# 1-Schematic_ESP32_expandable_Power.net
KiCad netlist of a schematic drawn in EasyEDA
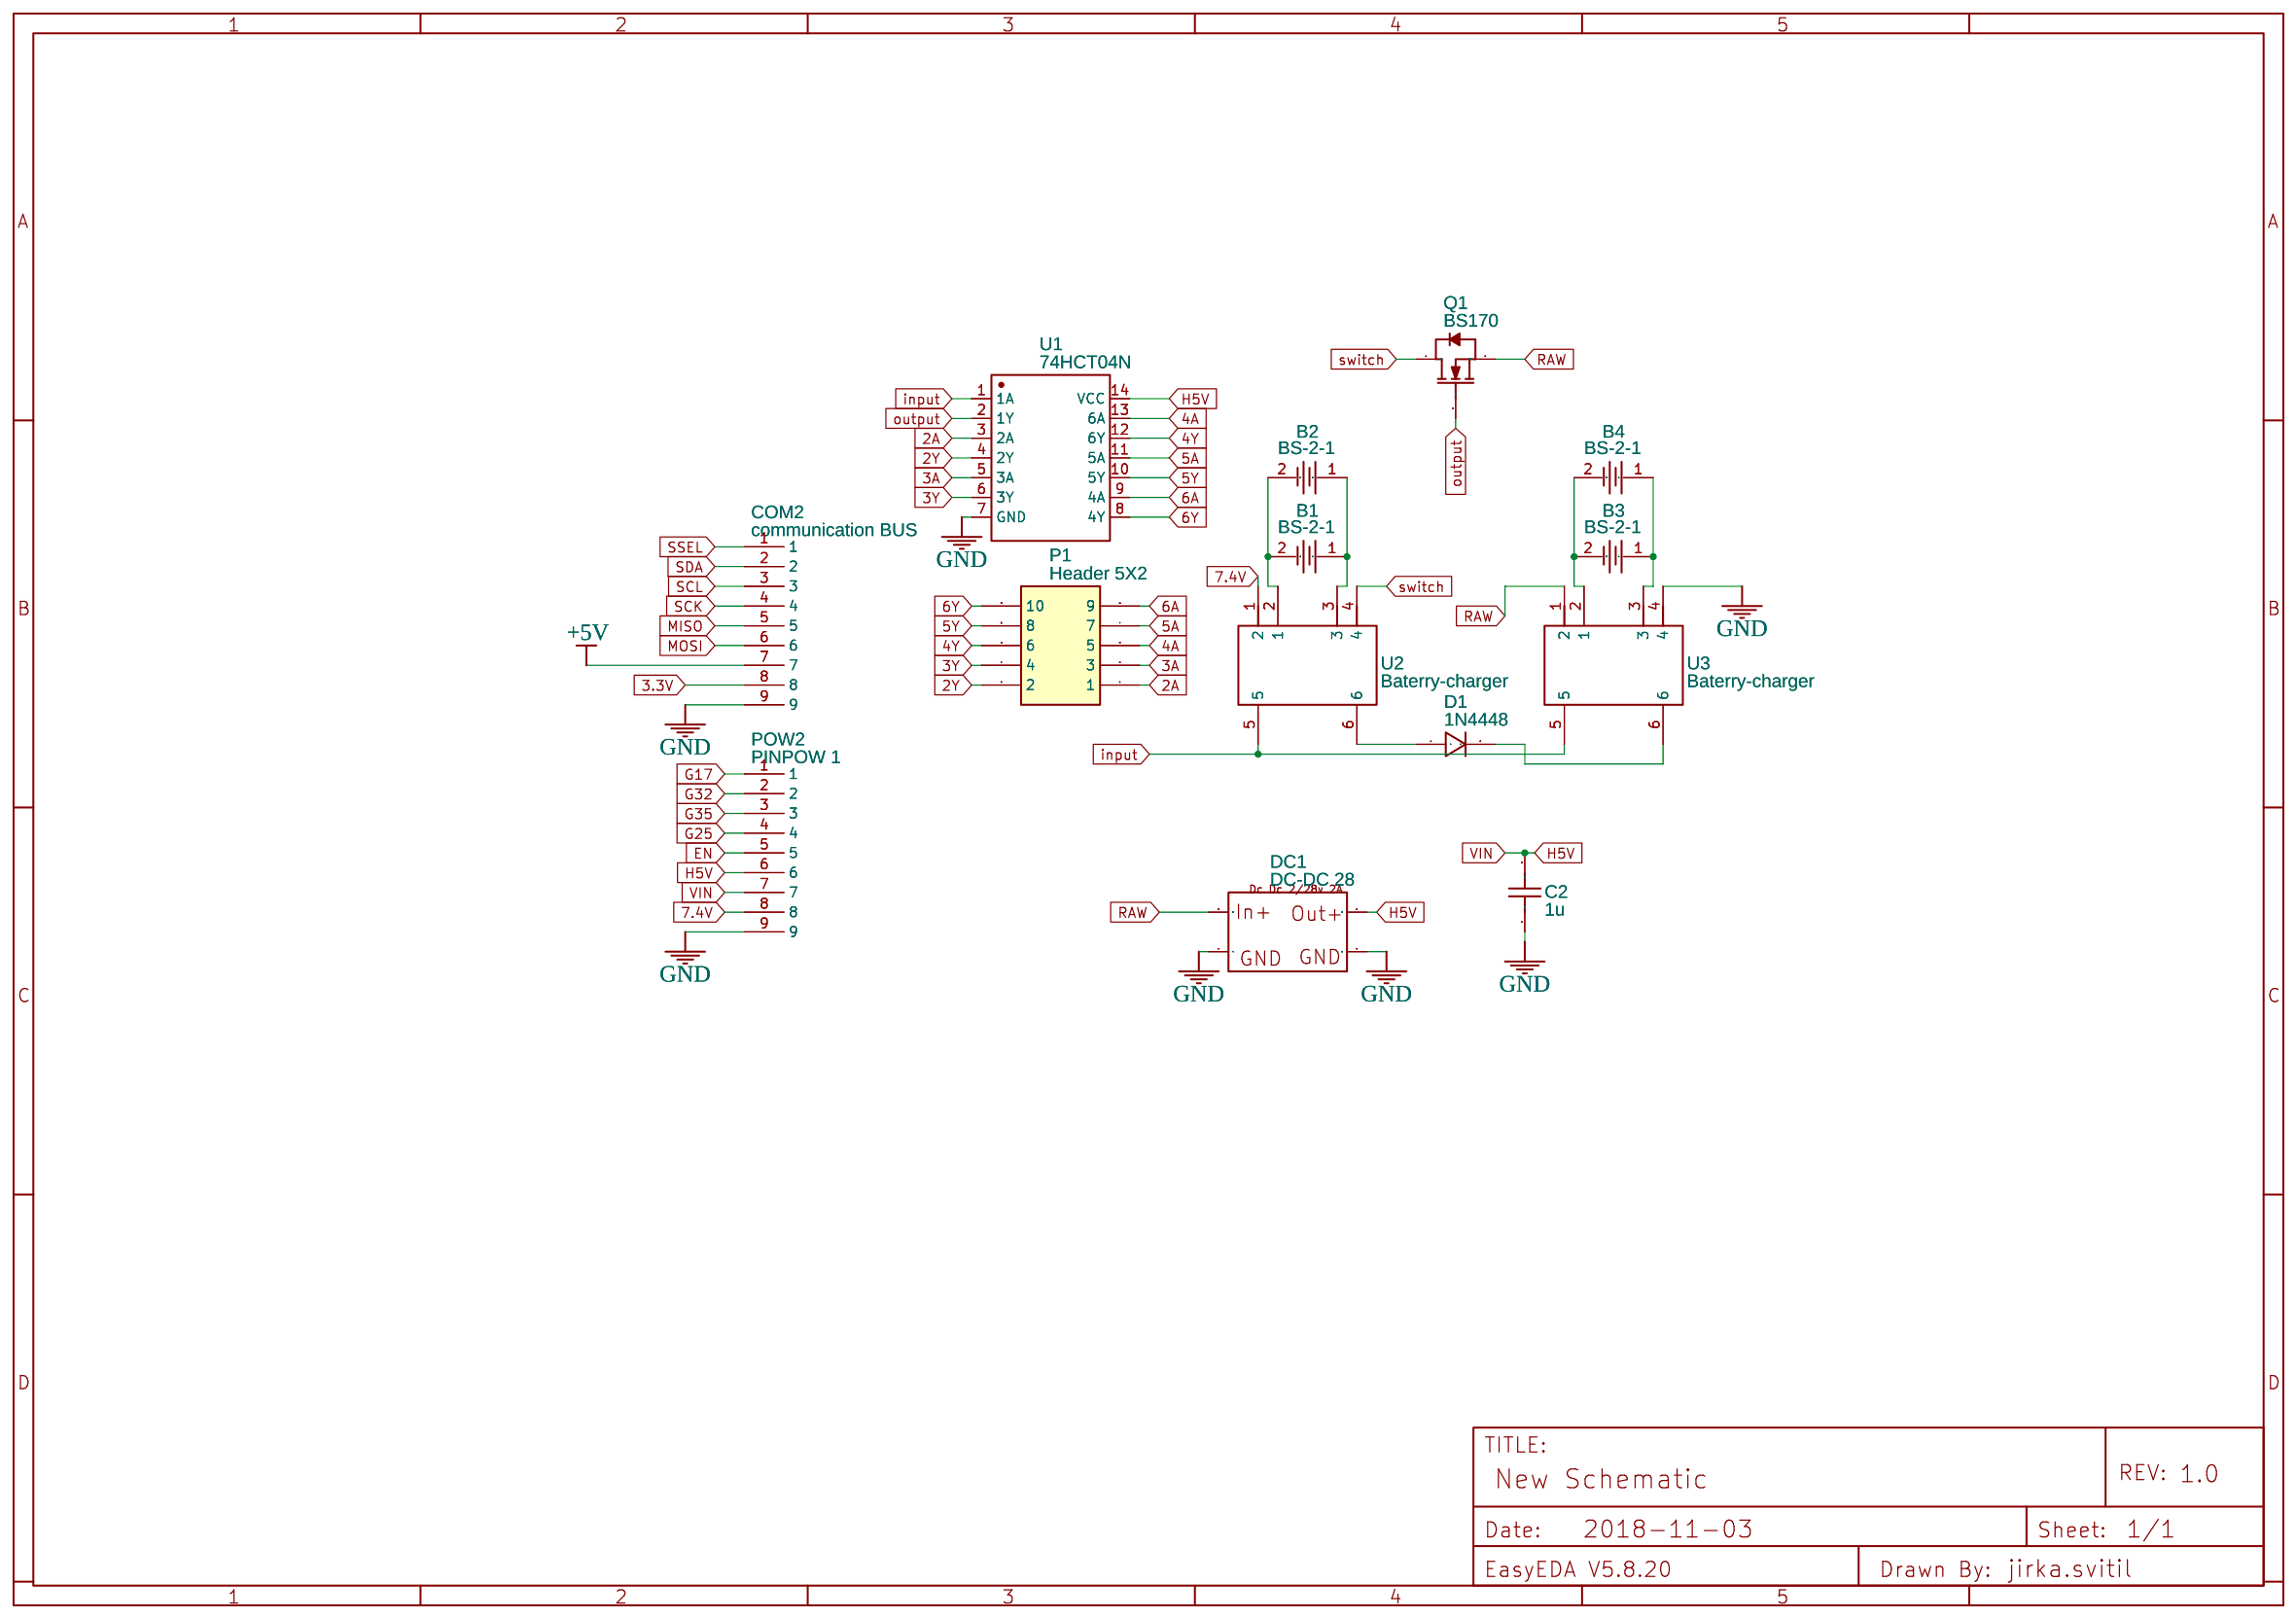
[diagram p0: schematic sheet]

(export (version "E")
  (design (tool "Eeschema 10.0.6"))
  (components
    (comp (ref "B1")
      (value "BS-2-1")
      (fields (field (name "BOM_Supplier Part") "C70376"))
      (libsource (lib "") (part "Unknown_655_275"))
    )
    (comp (ref "B2")
      (value "BS-2-1")
      (fields (field (name "BOM_Supplier Part") "C70376"))
      (libsource (lib "") (part "Unknown_655_235"))
    )
    (comp (ref "B3")
      (value "BS-2-1")
      (fields (field (name "BOM_Supplier Part") "C70376"))
      (libsource (lib "") (part "Unknown_810_275"))
    )
    (comp (ref "B4")
      (value "BS-2-1")
      (fields (field (name "BOM_Supplier Part") "C70376"))
      (libsource (lib "") (part "Unknown_810_235"))
    )
    (comp (ref "C2")
      (value "1u")
      (fields (field (name "BOM_Manufacturer Part") "?"))
      (libsource (lib "") (part "Cap_RAD-0.1_US"))
    )
    (comp (ref "COM2")
      (value "communication BUS")
      (fields (field (name "BOM_Manufacturer Part") "?"))
      (libsource (lib "") (part "Unknown_400_260"))
    )
    (comp (ref "D1")
      (value "1N4448")
      (fields (field (name "BOM_Supplier Part") "C54037"))
      (libsource (lib "") (part "Unknown_730_370"))
    )
    (comp (ref "DC1")
      (value "DC-DC 28")
      (fields (field (name "BOM_Manufacturer Part") "?"))
      (libsource (lib "") (part "DC-DC 28"))
    )
    (comp (ref "P1")
      (value "Header 5X2")
      (fields (field (name "BOM_Manufacturer Part") "?"))
      (libsource (lib "") (part "Unknown_530_320"))
    )
    (comp (ref "POW2")
      (value "PINPOW 1")
      (fields (field (name "BOM_Manufacturer Part") "?"))
      (libsource (lib "") (part "Unknown_400_375"))
    )
    (comp (ref "Q1")
      (value "BS170")
      (fields (field (name "BOM_Supplier Part") "C111691"))
      (libsource (lib "") (part "Unknown_730_175"))
    )
    (comp (ref "U1")
      (value "74HCT04N")
      (fields (field (name "BOM_Manufacturer Part") "?"))
      (libsource (lib "") (part "Unknown_525_185"))
    )
    (comp (ref "U2")
      (value "Baterry-charger")
      (fields (field (name "BOM_Manufacturer Part") "New SchematicLib"))
      (libsource (lib "") (part "Unknown_650_330"))
    )
    (comp (ref "U3")
      (value "Baterry-charger")
      (fields (field (name "BOM_Manufacturer Part") "New SchematicLib"))
      (libsource (lib "") (part "Unknown_805_330"))
    )
  )
  (nets
    (net (code "1") (name "+5V") (class "Default")
      (node (ref "COM2") (pin "7") (pinfunction "7_7") (pintype "unspecified"))
    )
    (net (code "2") (name "2A") (class "Default")
      (node (ref "P1") (pin "1") (pinfunction "1_1") (pintype "unspecified"))
      (node (ref "U1") (pin "3") (pinfunction "2A_3") (pintype "unspecified"))
    )
    (net (code "3") (name "2Y") (class "Default")
      (node (ref "P1") (pin "2") (pinfunction "2_2") (pintype "unspecified"))
      (node (ref "U1") (pin "4") (pinfunction "2Y_4") (pintype "unspecified"))
    )
    (net (code "4") (name "3.3V") (class "Default")
      (node (ref "COM2") (pin "8") (pinfunction "8_8") (pintype "unspecified"))
    )
    (net (code "5") (name "3A") (class "Default")
      (node (ref "P1") (pin "3") (pinfunction "3_3") (pintype "unspecified"))
      (node (ref "U1") (pin "5") (pinfunction "3A_5") (pintype "unspecified"))
    )
    (net (code "6") (name "3Y") (class "Default")
      (node (ref "P1") (pin "4") (pinfunction "4_4") (pintype "unspecified"))
      (node (ref "U1") (pin "6") (pinfunction "3Y_6") (pintype "unspecified"))
    )
    (net (code "7") (name "4A") (class "Default")
      (node (ref "P1") (pin "5") (pinfunction "5_5") (pintype "unspecified"))
      (node (ref "U1") (pin "13") (pinfunction "6A_13") (pintype "unspecified"))
    )
    (net (code "8") (name "4Y") (class "Default")
      (node (ref "P1") (pin "6") (pinfunction "6_6") (pintype "unspecified"))
      (node (ref "U1") (pin "12") (pinfunction "6Y_12") (pintype "unspecified"))
    )
    (net (code "9") (name "5A") (class "Default")
      (node (ref "P1") (pin "7") (pinfunction "7_7") (pintype "unspecified"))
      (node (ref "U1") (pin "11") (pinfunction "5A_11") (pintype "unspecified"))
    )
    (net (code "10") (name "5Y") (class "Default")
      (node (ref "P1") (pin "8") (pinfunction "8_8") (pintype "unspecified"))
      (node (ref "U1") (pin "10") (pinfunction "5Y_10") (pintype "unspecified"))
    )
    (net (code "11") (name "6A") (class "Default")
      (node (ref "P1") (pin "9") (pinfunction "9_9") (pintype "unspecified"))
      (node (ref "U1") (pin "9") (pinfunction "4A_9") (pintype "unspecified"))
    )
    (net (code "12") (name "6Y") (class "Default")
      (node (ref "P1") (pin "10") (pinfunction "10_10") (pintype "unspecified"))
      (node (ref "U1") (pin "8") (pinfunction "4Y_8") (pintype "unspecified"))
    )
    (net (code "13") (name "7.4V") (class "Default")
      (node (ref "POW2") (pin "8") (pinfunction "8_8") (pintype "unspecified"))
      (node (ref "U2") (pin "1") (pinfunction "2_1") (pintype "unspecified"))
    )
    (net (code "14") (name "EN") (class "Default")
      (node (ref "POW2") (pin "5") (pinfunction "5_5") (pintype "unspecified"))
    )
    (net (code "15") (name "G17") (class "Default")
      (node (ref "POW2") (pin "1") (pinfunction "1_1") (pintype "unspecified"))
    )
    (net (code "16") (name "G25") (class "Default")
      (node (ref "POW2") (pin "4") (pinfunction "4_4") (pintype "unspecified"))
    )
    (net (code "17") (name "G32") (class "Default")
      (node (ref "POW2") (pin "2") (pinfunction "2_2") (pintype "unspecified"))
    )
    (net (code "18") (name "G35") (class "Default")
      (node (ref "POW2") (pin "3") (pinfunction "3_3") (pintype "unspecified"))
    )
    (net (code "19") (name "GND") (class "Default")
      (node (ref "C2") (pin "1") (pinfunction "1_1") (pintype "unspecified"))
      (node (ref "COM2") (pin "9") (pinfunction "9_9") (pintype "unspecified"))
      (node (ref "DC1") (pin "2") (pinfunction "2_2") (pintype "unspecified"))
      (node (ref "DC1") (pin "4") (pinfunction "4_4") (pintype "unspecified"))
      (node (ref "POW2") (pin "9") (pinfunction "9_9") (pintype "unspecified"))
      (node (ref "U1") (pin "7") (pinfunction "GND_7") (pintype "unspecified"))
      (node (ref "U3") (pin "4") (pinfunction "4_4") (pintype "unspecified"))
    )
    (net (code "20") (name "H5V") (class "Default")
      (node (ref "C2") (pin "2") (pinfunction "2_2") (pintype "unspecified"))
      (node (ref "DC1") (pin "1") (pinfunction "1_1") (pintype "unspecified"))
      (node (ref "POW2") (pin "6") (pinfunction "6_6") (pintype "unspecified"))
      (node (ref "POW2") (pin "7") (pinfunction "7_7") (pintype "unspecified"))
      (node (ref "U1") (pin "14") (pinfunction "VCC_14") (pintype "unspecified"))
    )
    (net (code "21") (name "MISO") (class "Default")
      (node (ref "COM2") (pin "5") (pinfunction "5_5") (pintype "unspecified"))
    )
    (net (code "22") (name "MOSI") (class "Default")
      (node (ref "COM2") (pin "6") (pinfunction "6_6") (pintype "unspecified"))
    )
    (net (code "23") (name "Net-(B1-Pad1)") (class "Default")
      (node (ref "B1") (pin "1") (pinfunction "1_1") (pintype "input"))
      (node (ref "B2") (pin "1") (pinfunction "1_1") (pintype "input"))
      (node (ref "U2") (pin "3") (pinfunction "3_3") (pintype "unspecified"))
    )
    (net (code "24") (name "Net-(B3-Pad1)") (class "Default")
      (node (ref "B3") (pin "1") (pinfunction "1_1") (pintype "input"))
      (node (ref "B4") (pin "1") (pinfunction "1_1") (pintype "input"))
      (node (ref "U3") (pin "3") (pinfunction "3_3") (pintype "unspecified"))
    )
    (net (code "25") (name "Net-(D1-A)") (class "Default")
      (node (ref "D1") (pin "1") (pinfunction "A_1") (pintype "unspecified"))
      (node (ref "U2") (pin "6") (pinfunction "6_6") (pintype "unspecified"))
    )
    (net (code "26") (name "Net-(D1-K)") (class "Default")
      (node (ref "D1") (pin "2") (pinfunction "K_2") (pintype "unspecified"))
      (node (ref "U3") (pin "6") (pinfunction "6_6") (pintype "unspecified"))
    )
    (net (code "27") (name "Net-(U2-1)") (class "Default")
      (node (ref "B1") (pin "2") (pinfunction "2_2") (pintype "input"))
      (node (ref "B2") (pin "2") (pinfunction "2_2") (pintype "input"))
      (node (ref "U2") (pin "2") (pinfunction "1_2") (pintype "unspecified"))
    )
    (net (code "28") (name "Net-(U3-1)") (class "Default")
      (node (ref "B3") (pin "2") (pinfunction "2_2") (pintype "input"))
      (node (ref "B4") (pin "2") (pinfunction "2_2") (pintype "input"))
      (node (ref "U3") (pin "2") (pinfunction "1_2") (pintype "unspecified"))
    )
    (net (code "29") (name "RAW") (class "Default")
      (node (ref "DC1") (pin "3") (pinfunction "3_3") (pintype "unspecified"))
      (node (ref "Q1") (pin "3") (pinfunction "S_3") (pintype "unspecified"))
      (node (ref "U3") (pin "1") (pinfunction "2_1") (pintype "unspecified"))
    )
    (net (code "30") (name "SCK") (class "Default")
      (node (ref "COM2") (pin "4") (pinfunction "4_4") (pintype "unspecified"))
    )
    (net (code "31") (name "SCL") (class "Default")
      (node (ref "COM2") (pin "3") (pinfunction "3_3") (pintype "unspecified"))
    )
    (net (code "32") (name "SDA") (class "Default")
      (node (ref "COM2") (pin "2") (pinfunction "2_2") (pintype "unspecified"))
    )
    (net (code "33") (name "SSEL") (class "Default")
      (node (ref "COM2") (pin "1") (pinfunction "1_1") (pintype "unspecified"))
    )
    (net (code "34") (name "input") (class "Default")
      (node (ref "U1") (pin "1") (pinfunction "1A_1") (pintype "unspecified"))
      (node (ref "U2") (pin "5") (pinfunction "5_5") (pintype "unspecified"))
      (node (ref "U3") (pin "5") (pinfunction "5_5") (pintype "unspecified"))
    )
    (net (code "35") (name "output") (class "Default")
      (node (ref "Q1") (pin "2") (pinfunction "G_2") (pintype "unspecified"))
      (node (ref "U1") (pin "2") (pinfunction "1Y_2") (pintype "unspecified"))
    )
    (net (code "36") (name "switch") (class "Default")
      (node (ref "Q1") (pin "1") (pinfunction "D_1") (pintype "unspecified"))
      (node (ref "U2") (pin "4") (pinfunction "4_4") (pintype "unspecified"))
    )
  )
)
